# LED_Sockel.net
KiCad netlist of a schematic drawn in EAGLE
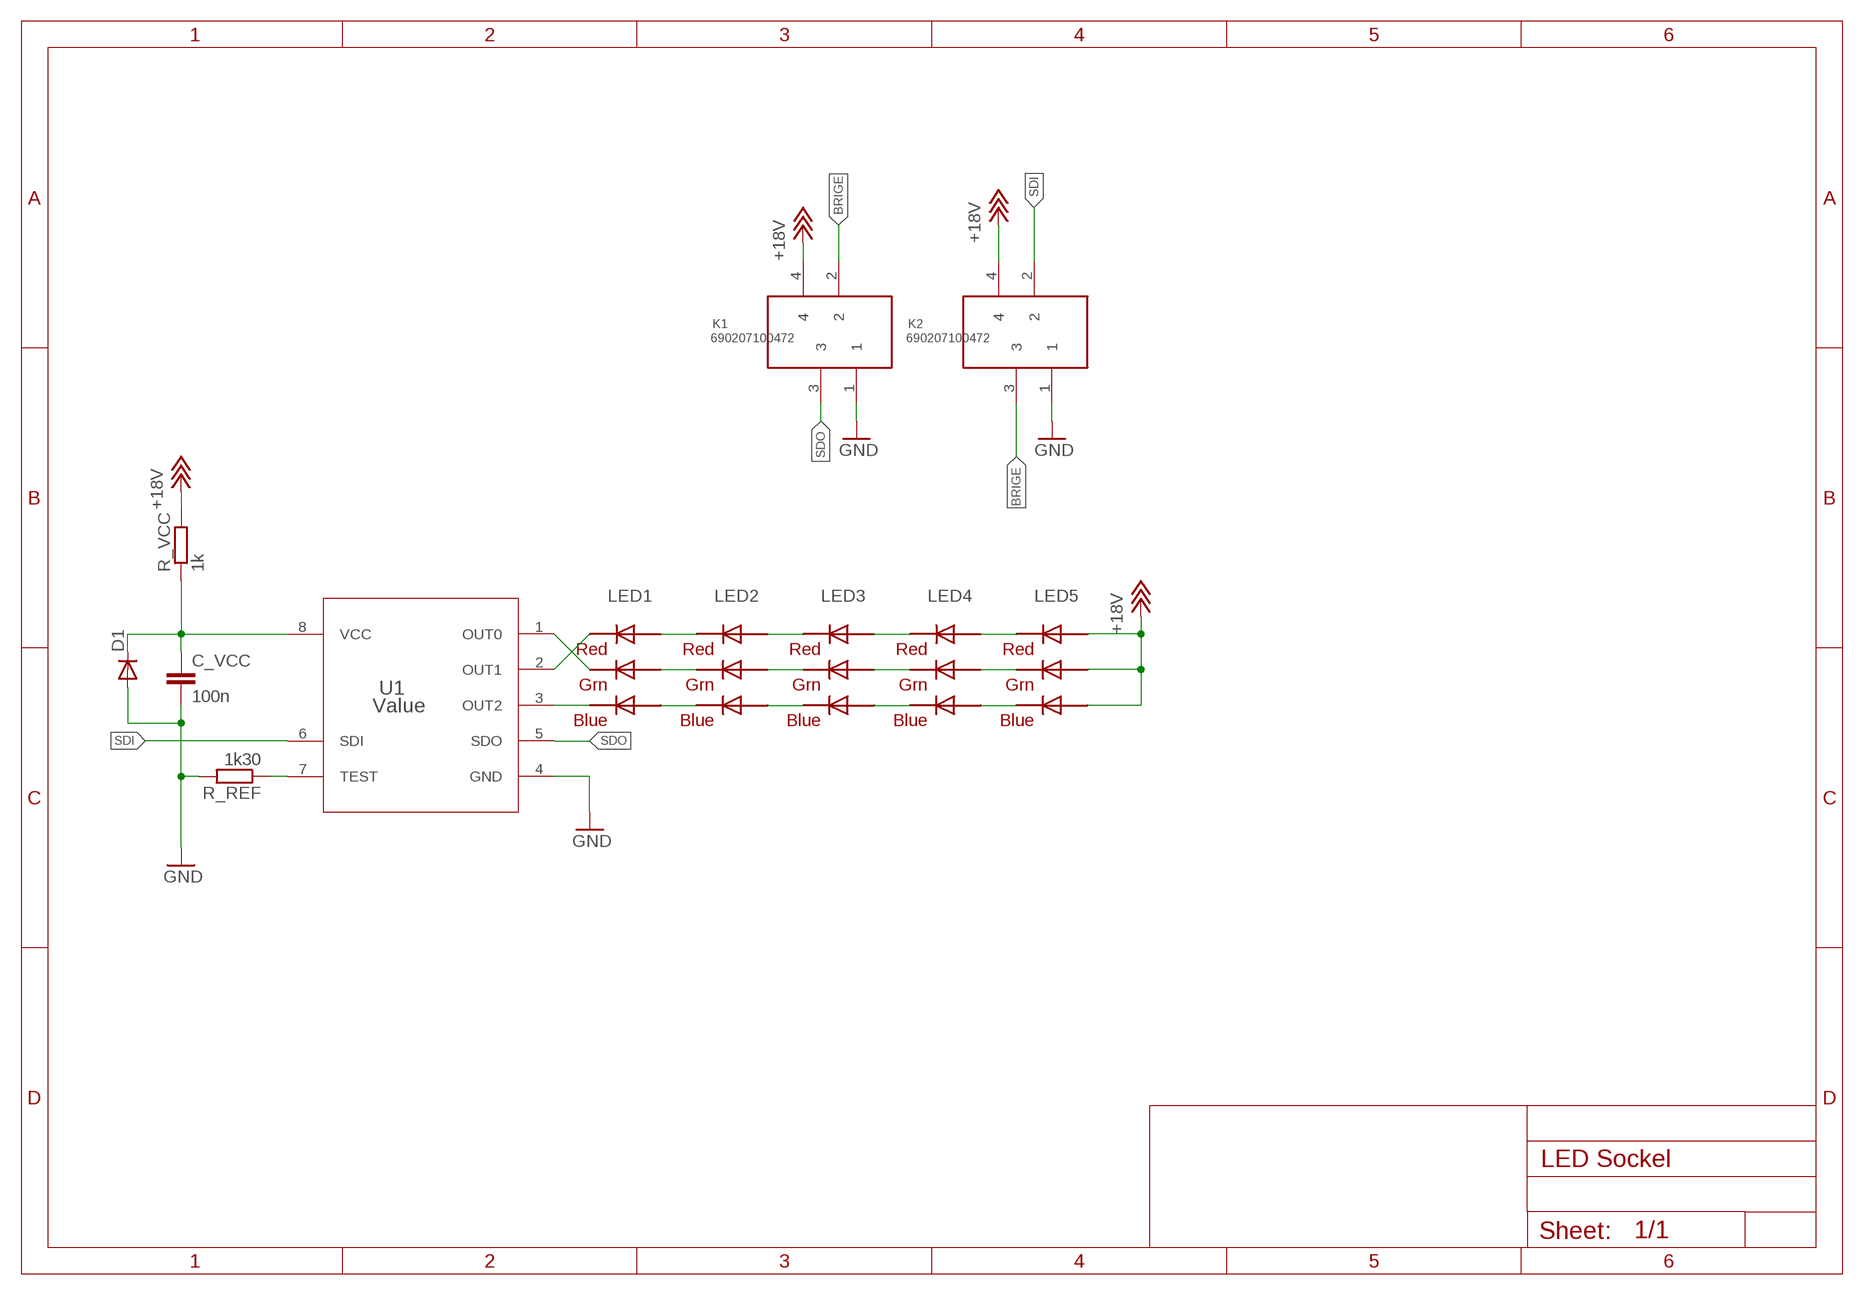
[diagram p0: schematic, sheet 1]

(export (version "E")
  (design (tool "Eeschema 10.0.6"))
  (components
    (comp (ref "C_VCC")
      (value "100n")
      (footprint "eagle-import:C0603")
      (libsource (lib "eagle-import") (part "C-EUC0603"))
    )
    (comp (ref "D1")
      (value "DIODE-SOD523")
      (footprint "eagle-import:SOD523")
      (libsource (lib "eagle-import") (part "DIODE-SOD523"))
    )
    (comp (ref "K1")
      (value "690207100472")
      (footprint "eagle-import:690207100472")
      (libsource (lib "eagle-import") (part "690207100472"))
    )
    (comp (ref "K2")
      (value "690207100472")
      (footprint "eagle-import:690207100472")
      (libsource (lib "eagle-import") (part "690207100472"))
    )
    (comp (ref "LED1")
      (value "RGBLED5050")
      (footprint "eagle-import:RGBLED5050")
      (libsource (lib "eagle-import") (part "RGBLED5050"))
    )
    (comp (ref "LED2")
      (value "RGBLED5050")
      (footprint "eagle-import:RGBLED5050")
      (libsource (lib "eagle-import") (part "RGBLED5050"))
    )
    (comp (ref "LED3")
      (value "RGBLED5050")
      (footprint "eagle-import:RGBLED5050")
      (libsource (lib "eagle-import") (part "RGBLED5050"))
    )
    (comp (ref "LED4")
      (value "RGBLED5050")
      (footprint "eagle-import:RGBLED5050")
      (libsource (lib "eagle-import") (part "RGBLED5050"))
    )
    (comp (ref "LED5")
      (value "RGBLED5050")
      (footprint "eagle-import:RGBLED5050")
      (libsource (lib "eagle-import") (part "RGBLED5050"))
    )
    (comp (ref "R_REF")
      (value "1k30")
      (footprint "eagle-import:R0603")
      (libsource (lib "eagle-import") (part "R-EU_R0603"))
    )
    (comp (ref "R_VCC")
      (value "1k")
      (footprint "eagle-import:R0805")
      (libsource (lib "eagle-import") (part "R-EU_R0805"))
    )
    (comp (ref "U1")
      (value "Value")
      (footprint "eagle-import:D0008A_N")
      (fields
        (field (name "ALTERNATEPARTNUMBER") "TLC59731D")
        (field (name "MANUFACTURER") "Texas Instruments")
        (field (name "PARTNUMBER") "TLC59731DR")
      )
      (libsource (lib "eagle-import") (part "TLC59731DR"))
    )
  )
  (nets
    (net (code "1") (name "+18V") (class "Default")
      (node (ref "K1") (pin "4") (pinfunction "4_4") (pintype "passive"))
      (node (ref "K2") (pin "4") (pinfunction "4_4") (pintype "passive"))
      (node (ref "LED5") (pin "1") (pinfunction "GREEN_A_1") (pintype "bidirectional"))
      (node (ref "LED5") (pin "2") (pinfunction "RED_A_2") (pintype "bidirectional"))
      (node (ref "LED5") (pin "3") (pinfunction "BLUE_A_3") (pintype "bidirectional"))
      (node (ref "R_VCC") (pin "2") (pinfunction "2_2") (pintype "passive"))
    )
    (net (code "2") (name "BRIGE") (class "Default")
      (node (ref "K1") (pin "2") (pinfunction "2_2") (pintype "passive"))
      (node (ref "K2") (pin "3") (pinfunction "3_3") (pintype "passive"))
    )
    (net (code "3") (name "GND") (class "Default")
      (node (ref "C_VCC") (pin "2") (pinfunction "2_2") (pintype "passive"))
      (node (ref "D1") (pin "A") (pinfunction "A_A") (pintype "passive"))
      (node (ref "K1") (pin "1") (pinfunction "1_1") (pintype "passive"))
      (node (ref "K2") (pin "1") (pinfunction "1_1") (pintype "passive"))
      (node (ref "R_REF") (pin "2") (pinfunction "2_2") (pintype "passive"))
      (node (ref "U1") (pin "4") (pinfunction "GND_4") (pintype "power_in"))
    )
    (net (code "4") (name "Net-(LED1-BLUE_A)") (class "Default")
      (node (ref "LED1") (pin "3") (pinfunction "BLUE_A_3") (pintype "bidirectional"))
      (node (ref "LED2") (pin "4") (pinfunction "BLUE_C_4") (pintype "bidirectional"))
    )
    (net (code "5") (name "Net-(LED1-BLUE_C)") (class "Default")
      (node (ref "LED1") (pin "4") (pinfunction "BLUE_C_4") (pintype "bidirectional"))
      (node (ref "U1") (pin "3") (pinfunction "OUT2_3") (pintype "output"))
    )
    (net (code "6") (name "Net-(LED1-GREEN_A)") (class "Default")
      (node (ref "LED1") (pin "1") (pinfunction "GREEN_A_1") (pintype "bidirectional"))
      (node (ref "LED2") (pin "6") (pinfunction "GREEN_C_6") (pintype "bidirectional"))
    )
    (net (code "7") (name "Net-(LED1-GREEN_C)") (class "Default")
      (node (ref "LED1") (pin "6") (pinfunction "GREEN_C_6") (pintype "bidirectional"))
      (node (ref "U1") (pin "1") (pinfunction "OUT0_1") (pintype "output"))
    )
    (net (code "8") (name "Net-(LED1-RED_A)") (class "Default")
      (node (ref "LED1") (pin "2") (pinfunction "RED_A_2") (pintype "bidirectional"))
      (node (ref "LED2") (pin "5") (pinfunction "RED_C_5") (pintype "bidirectional"))
    )
    (net (code "9") (name "Net-(LED1-RED_C)") (class "Default")
      (node (ref "LED1") (pin "5") (pinfunction "RED_C_5") (pintype "bidirectional"))
      (node (ref "U1") (pin "2") (pinfunction "OUT1_2") (pintype "output"))
    )
    (net (code "10") (name "Net-(LED2-BLUE_A)") (class "Default")
      (node (ref "LED2") (pin "3") (pinfunction "BLUE_A_3") (pintype "bidirectional"))
      (node (ref "LED3") (pin "4") (pinfunction "BLUE_C_4") (pintype "bidirectional"))
    )
    (net (code "11") (name "Net-(LED2-GREEN_A)") (class "Default")
      (node (ref "LED2") (pin "1") (pinfunction "GREEN_A_1") (pintype "bidirectional"))
      (node (ref "LED3") (pin "6") (pinfunction "GREEN_C_6") (pintype "bidirectional"))
    )
    (net (code "12") (name "Net-(LED2-RED_A)") (class "Default")
      (node (ref "LED2") (pin "2") (pinfunction "RED_A_2") (pintype "bidirectional"))
      (node (ref "LED3") (pin "5") (pinfunction "RED_C_5") (pintype "bidirectional"))
    )
    (net (code "13") (name "Net-(LED3-BLUE_A)") (class "Default")
      (node (ref "LED3") (pin "3") (pinfunction "BLUE_A_3") (pintype "bidirectional"))
      (node (ref "LED4") (pin "4") (pinfunction "BLUE_C_4") (pintype "bidirectional"))
    )
    (net (code "14") (name "Net-(LED3-GREEN_A)") (class "Default")
      (node (ref "LED3") (pin "1") (pinfunction "GREEN_A_1") (pintype "bidirectional"))
      (node (ref "LED4") (pin "6") (pinfunction "GREEN_C_6") (pintype "bidirectional"))
    )
    (net (code "15") (name "Net-(LED3-RED_A)") (class "Default")
      (node (ref "LED3") (pin "2") (pinfunction "RED_A_2") (pintype "bidirectional"))
      (node (ref "LED4") (pin "5") (pinfunction "RED_C_5") (pintype "bidirectional"))
    )
    (net (code "16") (name "Net-(LED4-BLUE_A)") (class "Default")
      (node (ref "LED4") (pin "3") (pinfunction "BLUE_A_3") (pintype "bidirectional"))
      (node (ref "LED5") (pin "4") (pinfunction "BLUE_C_4") (pintype "bidirectional"))
    )
    (net (code "17") (name "Net-(LED4-GREEN_A)") (class "Default")
      (node (ref "LED4") (pin "1") (pinfunction "GREEN_A_1") (pintype "bidirectional"))
      (node (ref "LED5") (pin "6") (pinfunction "GREEN_C_6") (pintype "bidirectional"))
    )
    (net (code "18") (name "Net-(LED4-RED_A)") (class "Default")
      (node (ref "LED4") (pin "2") (pinfunction "RED_A_2") (pintype "bidirectional"))
      (node (ref "LED5") (pin "5") (pinfunction "RED_C_5") (pintype "bidirectional"))
    )
    (net (code "19") (name "Net-(U1-TEST)") (class "Default")
      (node (ref "R_REF") (pin "1") (pinfunction "1_1") (pintype "passive"))
      (node (ref "U1") (pin "7") (pinfunction "TEST_7") (pintype "passive"))
    )
    (net (code "20") (name "Net-(U1-VCC)") (class "Default")
      (node (ref "C_VCC") (pin "1") (pinfunction "1_1") (pintype "passive"))
      (node (ref "D1") (pin "C") (pinfunction "C_C") (pintype "passive"))
      (node (ref "R_VCC") (pin "1") (pinfunction "1_1") (pintype "passive"))
      (node (ref "U1") (pin "8") (pinfunction "VCC_8") (pintype "power_in"))
    )
    (net (code "21") (name "SDI") (class "Default")
      (node (ref "K2") (pin "2") (pinfunction "2_2") (pintype "passive"))
      (node (ref "U1") (pin "6") (pinfunction "SDI_6") (pintype "input"))
    )
    (net (code "22") (name "SDO") (class "Default")
      (node (ref "K1") (pin "3") (pinfunction "3_3") (pintype "passive"))
      (node (ref "U1") (pin "5") (pinfunction "SDO_5") (pintype "output"))
    )
  )
)
